# N-CW7_PWR_TWB.net
KiCad netlist of a schematic drawn in Altium Designer
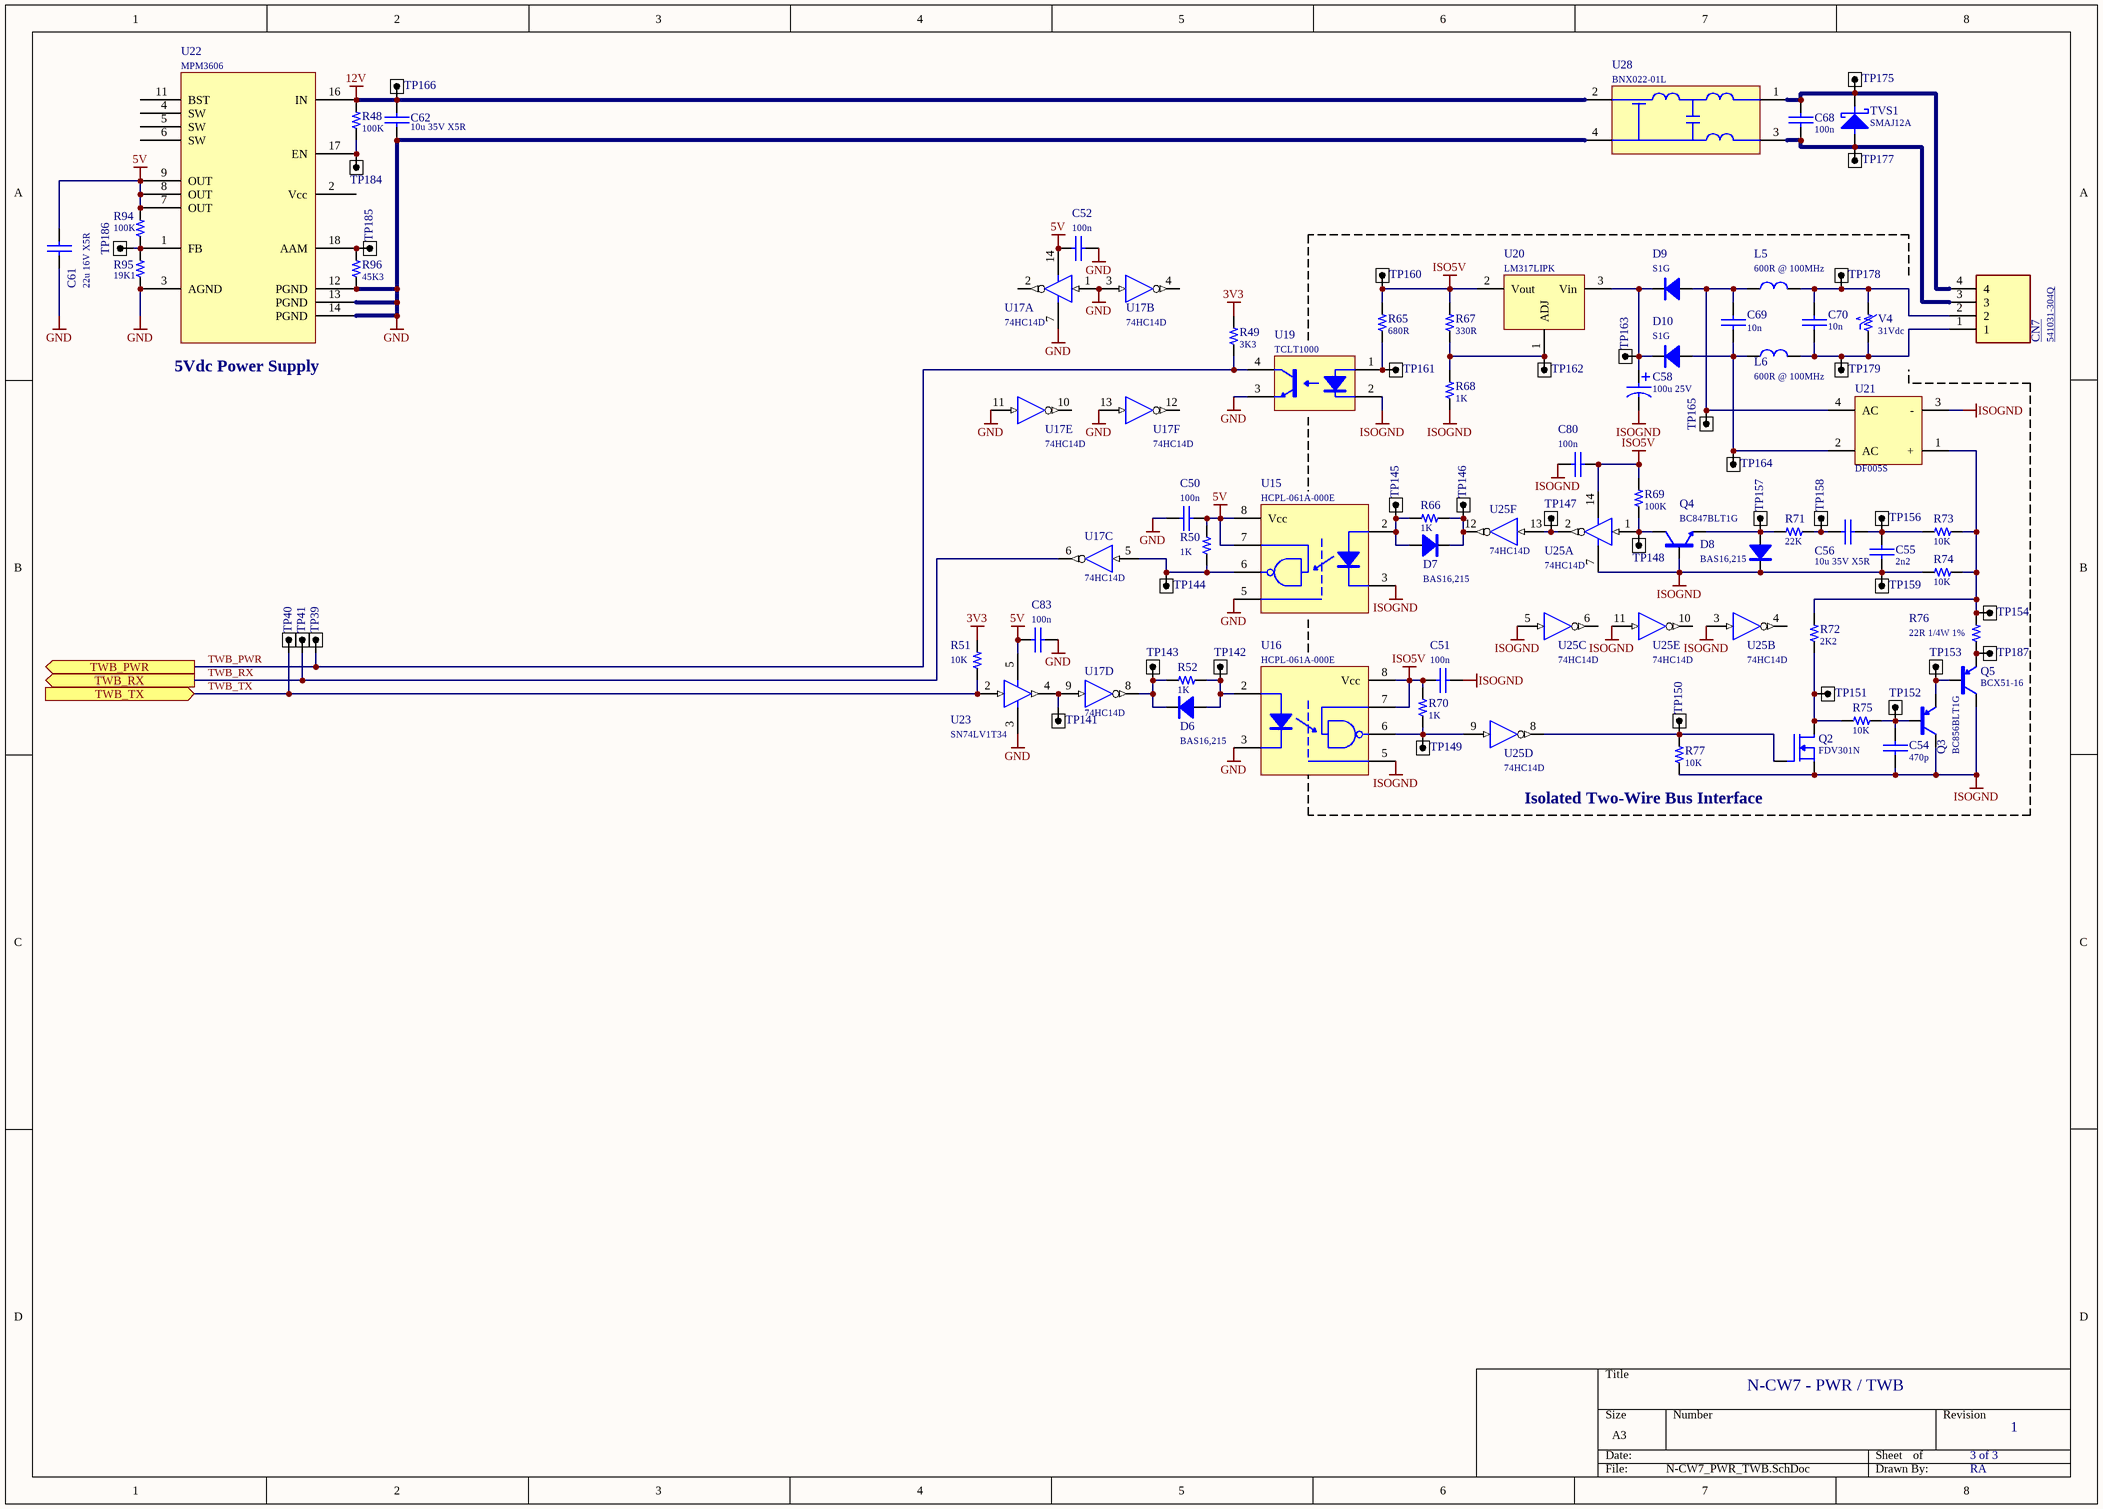
[diagram p0: N-CW7_PWR_TWB.SchDoc]

(export (version "E")
  (design (tool "Eeschema 10.0.6"))
  (components
    (comp (ref "C50")
      (value "100n")
      (footprint "TDK_0603_T0.80:CAPC1608X08N")
      (description "CAP CER 0.1UF 50V X7R 0603")
      (fields
        (field (name "MANUFACTURER") "TDK")
        (field (name "MANUFACTURER PART NUMBER") "C1608X7R1H104K080AA")
      )
      (libsource (lib "PassiveComponents_Capacitors_Ceramic") (part "TDK_0603_T0.80"))
    )
    (comp (ref "C51")
      (value "100n")
      (footprint "TDK_0603_T0.80:CAPC1608X08N")
      (description "CAP CER 0.1UF 50V X7R 0603")
      (fields
        (field (name "MANUFACTURER") "TDK")
        (field (name "MANUFACTURER PART NUMBER") "C1608X7R1H104K080AA")
      )
      (libsource (lib "PassiveComponents_Capacitors_Ceramic") (part "TDK_0603_T0.80"))
    )
    (comp (ref "C52")
      (value "100n")
      (footprint "TDK_0603_T0.80:CAPC1608X08N")
      (description "CAP CER 0.1UF 50V X7R 0603")
      (fields
        (field (name "MANUFACTURER") "TDK")
        (field (name "MANUFACTURER PART NUMBER") "C1608X7R1H104K080AA")
      )
      (libsource (lib "PassiveComponents_Capacitors_Ceramic") (part "TDK_0603_T0.80"))
    )
    (comp (ref "C54")
      (value "470p")
      (footprint "TDK_0603_T0.80:CAPC1608X08N")
      (description "CAP CER 470PF 50V C0G 0603")
      (fields
        (field (name "MANUFACTURER") "TDK")
        (field (name "MANUFACTURER PART NUMBER") "C1608C0G1H471J080AA")
      )
      (libsource (lib "PassiveComponents_Capacitors_Ceramic") (part "TDK_0603_T0.80"))
    )
    (comp (ref "C55")
      (value "2n2")
      (footprint "TDK_0603_T0.80:CAPC1608X08N")
      (description "CAP CER 2200PF 50V X7R 0603")
      (fields
        (field (name "MANUFACTURER") "TDK")
        (field (name "MANUFACTURER PART NUMBER") "C1608X7R1H222K080AE")
      )
      (libsource (lib "PassiveComponents_Capacitors_Ceramic") (part "TDK_0603_T0.80"))
    )
    (comp (ref "C56")
      (value "10u 35V X5R")
      (footprint "KEMET_1210_T1.90:CAPC3225X19N")
      (description "CAP CER 10UF 35V X5R 1210")
      (fields
        (field (name "MANUFACTURER") "KEMET")
        (field (name "MANUFACTURER PART NUMBER") "C1210C106K6PACTU")
      )
      (libsource (lib "PassiveComponents_Capacitors_Ceramic") (part "KEMET_1210_T1.90"))
    )
    (comp (ref "C58")
      (value "100u 25V")
      (footprint "KEMET_T494X/7343-43:CAPMP7343X43N")
      (description "CAP TANT 100UF 20% 25V 2917")
      (fields
        (field (name "MANUFACTURER") "KEMET")
        (field (name "MANUFACTURER PART NUMBER") "T494X107M025AT")
      )
      (libsource (lib "PassiveComponents_Capacitors_Tantalum") (part "KEMET_T494X/EIA7343-43"))
    )
    (comp (ref "C61")
      (value "22u 16V X5R")
      (footprint "TDK_0805_T1.25:CAPC2013X12N")
      (description "CAP CER 22UF 16V X5R 0805")
      (fields
        (field (name "MANUFACTURER") "TDK")
        (field (name "MANUFACTURER PART NUMBER") "C2012X5R1C226M085AC")
      )
      (libsource (lib "PassiveComponents_Capacitors_Ceramic") (part "TDK_0805_T1.25"))
    )
    (comp (ref "C62")
      (value "10u 35V X5R")
      (footprint "KEMET_1210_T1.90:CAPC3225X19N")
      (description "CAP CER 10UF 35V X5R 1210")
      (fields
        (field (name "MANUFACTURER") "KEMET")
        (field (name "MANUFACTURER PART NUMBER") "C1210C106K6PACTU")
      )
      (libsource (lib "PassiveComponents_Capacitors_Ceramic") (part "KEMET_1210_T1.90"))
    )
    (comp (ref "C68")
      (value "100n")
      (footprint "TDK_0603_T0.80:CAPC1608X08N")
      (description "CAP CER 0.1UF 50V X7R 0603")
      (fields
        (field (name "MANUFACTURER") "TDK")
        (field (name "MANUFACTURER PART NUMBER") "C1608X7R1H104K080AA")
      )
      (libsource (lib "PassiveComponents_Capacitors_Ceramic") (part "TDK_0603_T0.80"))
    )
    (comp (ref "C69")
      (value "10n")
      (footprint "TDK_0603_T0.80:CAPC1608X08N")
      (description "CAP CER 10000PF 50V X7R 0603")
      (fields
        (field (name "MANUFACTURER") "TDK")
        (field (name "MANUFACTURER PART NUMBER") "C1608X7R1H103K080AA")
      )
      (libsource (lib "PassiveComponents_Capacitors_Ceramic") (part "TDK_0603_T0.80"))
    )
    (comp (ref "C70")
      (value "10n")
      (footprint "TDK_0603_T0.80:CAPC1608X08N")
      (description "CAP CER 10000PF 50V X7R 0603")
      (fields
        (field (name "MANUFACTURER") "TDK")
        (field (name "MANUFACTURER PART NUMBER") "C1608X7R1H103K080AA")
      )
      (libsource (lib "PassiveComponents_Capacitors_Ceramic") (part "TDK_0603_T0.80"))
    )
    (comp (ref "C80")
      (value "100n")
      (footprint "TDK_0603_T0.80:CAPC1608X08N")
      (description "CAP CER 0.1UF 50V X7R 0603")
      (fields
        (field (name "MANUFACTURER") "TDK")
        (field (name "MANUFACTURER PART NUMBER") "C1608X7R1H104K080AA")
      )
      (libsource (lib "PassiveComponents_Capacitors_Ceramic") (part "TDK_0603_T0.80"))
    )
    (comp (ref "C83")
      (value "100n")
      (footprint "TDK_0603_T0.80:CAPC1608X08N")
      (description "CAP CER 0.1UF 50V X7R 0603")
      (fields
        (field (name "MANUFACTURER") "TDK")
        (field (name "MANUFACTURER PART NUMBER") "C1608X7R1H104K080AA")
      )
      (libsource (lib "PassiveComponents_Capacitors_Ceramic") (part "TDK_0603_T0.80"))
    )
    (comp (ref "CN7")
      (value "541031-304Q")
      (footprint "JWT_A2501WR2-4P:PS2.50MM")
      (description "A2501WR2-4P (JWT) 2.50mm Pitch (R-DIP)")
      (libsource (lib "Connectors") (part "JWT_A2501WR2-4P"))
    )
    (comp (ref "D6")
      (value "BAS16,215")
      (footprint "NEXPERIA_BAS16,215_SOT_23:SOT95P230X110-3N")
      (description "DIODE GP 100V 215MA SOT23")
      (fields (field (name "MANUFACTURER") "Nexperia"))
      (libsource (lib "DiscreteSemiconductors_Diodes_Rectifier") (part "NEXPERIA_BAS16,215_SOT23"))
    )
    (comp (ref "D7")
      (value "BAS16,215")
      (footprint "NEXPERIA_BAS16,215_SOT_23:SOT95P230X110-3N")
      (description "DIODE GP 100V 215MA SOT23")
      (fields (field (name "MANUFACTURER") "Nexperia"))
      (libsource (lib "DiscreteSemiconductors_Diodes_Rectifier") (part "NEXPERIA_BAS16,215_SOT23"))
    )
    (comp (ref "D8")
      (value "BAS16,215")
      (footprint "NEXPERIA_BAS16,215_SOT_23:SOT95P230X110-3N")
      (description "DIODE GP 100V 215MA SOT23")
      (fields (field (name "MANUFACTURER") "Nexperia"))
      (libsource (lib "DiscreteSemiconductors_Diodes_Rectifier") (part "NEXPERIA_BAS16,215_SOT23"))
    )
    (comp (ref "D9")
      (value "S1G")
      (footprint "DIODESINC_S1G_SMA_D0214AC:DIOM4326X24N")
      (description "DIODE GEN PURP 400V 1A SMA")
      (fields (field (name "MANUFACTURER") "Diodes") (field (name "MANUFACTURER PART NUMBER") "S1G-13-F"))
      (libsource (lib "DiscreteSemiconductors_Diodes_Rectifier") (part "DIODESINC_S1G_SMA_D0214AC"))
    )
    (comp (ref "D10")
      (value "S1G")
      (footprint "DIODESINC_S1G_SMA_D0214AC:DIOM4326X24N")
      (description "DIODE GEN PURP 400V 1A SMA")
      (fields (field (name "MANUFACTURER") "Diodes") (field (name "MANUFACTURER PART NUMBER") "S1G-13-F"))
      (libsource (lib "DiscreteSemiconductors_Diodes_Rectifier") (part "DIODESINC_S1G_SMA_D0214AC"))
    )
    (comp (ref "L5")
      (value "600R @ 100MHz")
      (footprint "LAIRD_MI0805K601R-10:INDC2012X09N")
      (description "FERRITE BEAD 600 OHM 0805 1LN")
      (fields
        (field (name "MANUFACTURER") "Laird")
        (field (name "MANUFACTURER PART NUMBER") "MI0805K601R-10")
      )
      (libsource (lib "PassiveComponents_Inductors") (part "LAIRD_MI0805K601R-10"))
    )
    (comp (ref "L6")
      (value "600R @ 100MHz")
      (footprint "LAIRD_MI0805K601R-10:INDC2012X09N")
      (description "FERRITE BEAD 600 OHM 0805 1LN")
      (fields
        (field (name "MANUFACTURER") "Laird")
        (field (name "MANUFACTURER PART NUMBER") "MI0805K601R-10")
      )
      (libsource (lib "PassiveComponents_Inductors") (part "LAIRD_MI0805K601R-10"))
    )
    (comp (ref "Q2")
      (value "FDV301N")
      (footprint "ONSEMI_FDV301N_SOT23:SOT95P230X110-3N")
      (description "MOSFET N-CH 25V 220MA SOT23")
      (fields (field (name "MANUFACTURER") "ON Semiconductor / Fairchild"))
      (libsource (lib "DiscreteSemiconductors_Transistors_JFETs") (part "ONSEMI_FDV301N_SOT23"))
    )
    (comp (ref "Q3")
      (value "BC856BLT1G")
      (footprint "ONSEMI_BC856BLT1G_SOT23_SOT95P237X110-3N")
      (description "TRANS PNP 65V 100MA SOT23-3")
      (fields (field (name "MANUFACTURER") "ON Semiconductor"))
      (libsource (lib "DiscreteSemiconductors_Transistors_BJTs") (part "ONSEMI_BC856BLT1G_SOT23"))
    )
    (comp (ref "Q4")
      (value "BC847BLT1G")
      (footprint "ONSEMI_BC847BLT1G_SOT23:SOT95P230X110-3N")
      (description "TRANS NPN 45V 100MA SOT23-3")
      (fields (field (name "MANUFACTURER") "ON Semiconductor"))
      (libsource (lib "DiscreteSemiconductors_Transistors_BJTs") (part "ONSEMI_BC847BLT1G_SOT23"))
    )
    (comp (ref "Q5")
      (value "BCX51-16")
      (footprint "INFINEON_BCX51-16_SOT89:SOT89-150P400X150-3N")
      (description "Bipolar (BJT) Transistor PNP 45 V 1 A 125MHz 2 W Surface Mount PG-SOT89")
      (fields (field (name "MANUFACTURER") "Infineon"))
      (libsource (lib "DiscreteSemiconductors_Transistors_BJTs") (part "INFINEON_BCX51-16_SOT89"))
    )
    (comp (ref "R48")
      (value "100K")
      (footprint "YAGEO_0603_T0.55:RESC1608X06N")
      (description "RES 100K OHM 1% 1/10W 0603")
      (fields
        (field (name "MANUFACTURER") "Yageo")
        (field (name "MANUFACTURER PART NUMBER") "RC0603FR-07100KL")
      )
      (libsource (lib "PassiveComponents_Resistors_ChipSMD") (part "YAGEO_0603_T0.55"))
    )
    (comp (ref "R49")
      (value "3K3")
      (footprint "YAGEO_0603_T0.55:RESC1608X06N")
      (description "RC0603FR-07XXXL")
      (fields
        (field (name "MANUFACTURER") "Yageo")
        (field (name "MANUFACTURER PART NUMBER") "RC0603FR-073K3L")
      )
      (libsource (lib "PassiveComponents_Resistors_ChipSMD") (part "YAGEO_0603_T0.55"))
    )
    (comp (ref "R50")
      (value "1K")
      (footprint "YAGEO_0603_T0.55:RESC1608X06N")
      (description "RES 1K OHM 1% 1/10W 0603")
      (fields
        (field (name "MANUFACTURER") "Yageo")
        (field (name "MANUFACTURER PART NUMBER") "RC0603FR-071KL")
      )
      (libsource (lib "PassiveComponents_Resistors_ChipSMD") (part "YAGEO_0603_T0.55"))
    )
    (comp (ref "R51")
      (value "10K")
      (footprint "YAGEO_0603_T0.55:RESC1608X06N")
      (description "RES 10K OHM 1% 1/10W 0603")
      (fields
        (field (name "MANUFACTURER") "Yageo")
        (field (name "MANUFACTURER PART NUMBER") "RC0603FR-0710KL")
      )
      (libsource (lib "PassiveComponents_Resistors_ChipSMD") (part "YAGEO_0603_T0.55"))
    )
    (comp (ref "R52")
      (value "1K")
      (footprint "YAGEO_0603_T0.55:RESC1608X06N")
      (description "RES 1K OHM 1% 1/10W 0603")
      (fields
        (field (name "MANUFACTURER") "Yageo")
        (field (name "MANUFACTURER PART NUMBER") "RC0603FR-071KL")
      )
      (libsource (lib "PassiveComponents_Resistors_ChipSMD") (part "YAGEO_0603_T0.55"))
    )
    (comp (ref "R65")
      (value "680R")
      (footprint "YAGEO_0603_T0.55:RESC1608X06N")
      (description "RES 680 OHM 1% 1/10W 0603")
      (fields
        (field (name "MANUFACTURER") "Yageo")
        (field (name "MANUFACTURER PART NUMBER") "RC0603FR-07680RL")
      )
      (libsource (lib "PassiveComponents_Resistors_ChipSMD") (part "YAGEO_0603_T0.55"))
    )
    (comp (ref "R66")
      (value "1K")
      (footprint "YAGEO_0603_T0.55:RESC1608X06N")
      (description "RES 1K OHM 1% 1/10W 0603")
      (fields
        (field (name "MANUFACTURER") "Yageo")
        (field (name "MANUFACTURER PART NUMBER") "RC0603FR-071KL")
      )
      (libsource (lib "PassiveComponents_Resistors_ChipSMD") (part "YAGEO_0603_T0.55"))
    )
    (comp (ref "R67")
      (value "330R")
      (footprint "YAGEO_0603_T0.55:RESC1608X06N")
      (description "RES 330 OHM 1% 1/10W 0603")
      (fields
        (field (name "MANUFACTURER") "Yageo")
        (field (name "MANUFACTURER PART NUMBER") "RC0603FR-07330RL")
      )
      (libsource (lib "PassiveComponents_Resistors_ChipSMD") (part "YAGEO_0603_T0.55"))
    )
    (comp (ref "R68")
      (value "1K")
      (footprint "YAGEO_0603_T0.55:RESC1608X06N")
      (description "RES 1K OHM 1% 1/10W 0603")
      (fields
        (field (name "MANUFACTURER") "Yageo")
        (field (name "MANUFACTURER PART NUMBER") "RC0603FR-071KL")
      )
      (libsource (lib "PassiveComponents_Resistors_ChipSMD") (part "YAGEO_0603_T0.55"))
    )
    (comp (ref "R69")
      (value "100K")
      (footprint "YAGEO_0603_T0.55:RESC1608X06N")
      (description "RES 100K OHM 1% 1/10W 0603")
      (fields
        (field (name "MANUFACTURER") "Yageo")
        (field (name "MANUFACTURER PART NUMBER") "RC0603FR-07100KL")
      )
      (libsource (lib "PassiveComponents_Resistors_ChipSMD") (part "YAGEO_0603_T0.55"))
    )
    (comp (ref "R70")
      (value "1K")
      (footprint "YAGEO_0603_T0.55:RESC1608X06N")
      (description "RES 1K OHM 1% 1/10W 0603")
      (fields
        (field (name "MANUFACTURER") "Yageo")
        (field (name "MANUFACTURER PART NUMBER") "RC0603FR-071KL")
      )
      (libsource (lib "PassiveComponents_Resistors_ChipSMD") (part "YAGEO_0603_T0.55"))
    )
    (comp (ref "R71")
      (value "22K")
      (footprint "YAGEO_0603_T0.55:RESC1608X06N")
      (description "RES 22K OHM 1% 1/10W 0603")
      (fields
        (field (name "MANUFACTURER") "Yageo")
        (field (name "MANUFACTURER PART NUMBER") "RC0603FR-0722KL")
      )
      (libsource (lib "PassiveComponents_Resistors_ChipSMD") (part "YAGEO_0603_T0.55"))
    )
    (comp (ref "R72")
      (value "2K2")
      (footprint "YAGEO_0603_T0.55:RESC1608X06N")
      (description "RES 2.2K OHM 1% 1/10W 0603")
      (fields
        (field (name "MANUFACTURER") "Yageo")
        (field (name "MANUFACTURER PART NUMBER") "RC0603FR-072K2L")
      )
      (libsource (lib "PassiveComponents_Resistors_ChipSMD") (part "YAGEO_0603_T0.55"))
    )
    (comp (ref "R73")
      (value "10K")
      (footprint "YAGEO_0603_T0.55:RESC1608X06N")
      (description "RES 10K OHM 1% 1/10W 0603")
      (fields
        (field (name "MANUFACTURER") "Yageo")
        (field (name "MANUFACTURER PART NUMBER") "RC0603FR-0710KL")
      )
      (libsource (lib "PassiveComponents_Resistors_ChipSMD") (part "YAGEO_0603_T0.55"))
    )
    (comp (ref "R74")
      (value "10K")
      (footprint "YAGEO_0603_T0.55:RESC1608X06N")
      (description "RES 10K OHM 1% 1/10W 0603")
      (fields
        (field (name "MANUFACTURER") "Yageo")
        (field (name "MANUFACTURER PART NUMBER") "RC0603FR-0710KL")
      )
      (libsource (lib "PassiveComponents_Resistors_ChipSMD") (part "YAGEO_0603_T0.55"))
    )
    (comp (ref "R75")
      (value "10K")
      (footprint "YAGEO_0603_T0.55:RESC1608X06N")
      (description "RES 10K OHM 1% 1/10W 0603")
      (fields
        (field (name "MANUFACTURER") "Yageo")
        (field (name "MANUFACTURER PART NUMBER") "RC0603FR-0710KL")
      )
      (libsource (lib "PassiveComponents_Resistors_ChipSMD") (part "YAGEO_0603_T0.55"))
    )
    (comp (ref "R76")
      (value "22R 1/4W 1%")
      (footprint "YAGEO_1206_T0.55:RESC3116X06N")
      (description "RES 22 OHM 1% 1/4W 1206")
      (fields
        (field (name "MANUFACTURER") "Yageo")
        (field (name "MANUFACTURER PART NUMBER") "RC1206FR-0722RL")
      )
      (libsource (lib "PassiveComponents_Resistors_ChipSMD") (part "YAGEO_1206_T0.55"))
    )
    (comp (ref "R77")
      (value "10K")
      (footprint "YAGEO_0603_T0.55:RESC1608X06N")
      (description "RES 10K OHM 1% 1/10W 0603")
      (fields
        (field (name "MANUFACTURER") "Yageo")
        (field (name "MANUFACTURER PART NUMBER") "RC0603FR-0710KL")
      )
      (libsource (lib "PassiveComponents_Resistors_ChipSMD") (part "YAGEO_0603_T0.55"))
    )
    (comp (ref "R94")
      (value "100K")
      (footprint "YAGEO_0603_T0.55:RESC1608X06N")
      (description "RES 100K OHM 1% 1/10W 0603")
      (fields
        (field (name "MANUFACTURER") "Yageo")
        (field (name "MANUFACTURER PART NUMBER") "RC0603FR-07100KL")
      )
      (libsource (lib "PassiveComponents_Resistors_ChipSMD") (part "YAGEO_0603_T0.55"))
    )
    (comp (ref "R95")
      (value "19K1")
      (footprint "YAGEO_0603_T0.55:RESC1608X06N")
      (description "RES 19.1K OHM 1% 1/10W 0603")
      (fields
        (field (name "MANUFACTURER") "Yageo")
        (field (name "MANUFACTURER PART NUMBER") "RC0603FR-0719K1L")
      )
      (libsource (lib "PassiveComponents_Resistors_ChipSMD") (part "YAGEO_0603_T0.55"))
    )
    (comp (ref "R96")
      (value "45K3")
      (footprint "YAGEO_0603_T0.55:RESC1608X06N")
      (description "RES 45.3K OHM 1% 1/10W 0603")
      (fields
        (field (name "MANUFACTURER") "Yageo")
        (field (name "MANUFACTURER PART NUMBER") "RC0603FR-0745K3L")
      )
      (libsource (lib "PassiveComponents_Resistors_ChipSMD") (part "YAGEO_0603_T0.55"))
    )
    (comp (ref "TP39")
      (value "TESTPOINT_OCTAGONAL")
      (footprint "TESTPOINT_OCTAGONAL")
      (libsource (lib "Miscellaneous") (part "TESTPOINT_OCTAGONAL"))
    )
    (comp (ref "TP40")
      (value "TESTPOINT_OCTAGONAL")
      (footprint "TESTPOINT_OCTAGONAL")
      (libsource (lib "Miscellaneous") (part "TESTPOINT_OCTAGONAL"))
    )
    (comp (ref "TP41")
      (value "TESTPOINT_OCTAGONAL")
      (footprint "TESTPOINT_OCTAGONAL")
      (libsource (lib "Miscellaneous") (part "TESTPOINT_OCTAGONAL"))
    )
    (comp (ref "TP141")
      (value "TESTPOINT_OCTAGONAL")
      (footprint "TESTPOINT_OCTAGONAL")
      (libsource (lib "") (part "TESTPOINT_OCTAGONAL_2"))
    )
    (comp (ref "TP142")
      (value "TESTPOINT_OCTAGONAL")
      (footprint "TESTPOINT_OCTAGONAL")
      (libsource (lib "Miscellaneous") (part "TESTPOINT_OCTAGONAL"))
    )
    (comp (ref "TP143")
      (value "TESTPOINT_OCTAGONAL")
      (footprint "TESTPOINT_OCTAGONAL")
      (libsource (lib "Miscellaneous") (part "TESTPOINT_OCTAGONAL"))
    )
    (comp (ref "TP144")
      (value "TESTPOINT_OCTAGONAL")
      (footprint "TESTPOINT_OCTAGONAL")
      (libsource (lib "") (part "TESTPOINT_OCTAGONAL_2"))
    )
    (comp (ref "TP145")
      (value "TESTPOINT_OCTAGONAL")
      (footprint "TESTPOINT_OCTAGONAL")
      (libsource (lib "Miscellaneous") (part "TESTPOINT_OCTAGONAL"))
    )
    (comp (ref "TP146")
      (value "TESTPOINT_OCTAGONAL")
      (footprint "TESTPOINT_OCTAGONAL")
      (libsource (lib "Miscellaneous") (part "TESTPOINT_OCTAGONAL"))
    )
    (comp (ref "TP147")
      (value "TESTPOINT_OCTAGONAL")
      (footprint "TESTPOINT_OCTAGONAL")
      (libsource (lib "Miscellaneous") (part "TESTPOINT_OCTAGONAL"))
    )
    (comp (ref "TP148")
      (value "TESTPOINT_OCTAGONAL")
      (footprint "TESTPOINT_OCTAGONAL")
      (libsource (lib "") (part "TESTPOINT_OCTAGONAL_2"))
    )
    (comp (ref "TP149")
      (value "TESTPOINT_OCTAGONAL")
      (footprint "TESTPOINT_OCTAGONAL")
      (libsource (lib "") (part "TESTPOINT_OCTAGONAL_2"))
    )
    (comp (ref "TP150")
      (value "TESTPOINT_OCTAGONAL")
      (footprint "TESTPOINT_OCTAGONAL")
      (libsource (lib "Miscellaneous") (part "TESTPOINT_OCTAGONAL"))
    )
    (comp (ref "TP151")
      (value "TESTPOINT_OCTAGONAL")
      (footprint "TESTPOINT_OCTAGONAL")
      (libsource (lib "") (part "TESTPOINT_OCTAGONAL_3"))
    )
    (comp (ref "TP152")
      (value "TESTPOINT_OCTAGONAL")
      (footprint "TESTPOINT_OCTAGONAL")
      (libsource (lib "Miscellaneous") (part "TESTPOINT_OCTAGONAL"))
    )
    (comp (ref "TP153")
      (value "TESTPOINT_OCTAGONAL")
      (footprint "TESTPOINT_OCTAGONAL")
      (libsource (lib "Miscellaneous") (part "TESTPOINT_OCTAGONAL"))
    )
    (comp (ref "TP154")
      (value "TESTPOINT_OCTAGONAL")
      (footprint "TESTPOINT_OCTAGONAL")
      (libsource (lib "") (part "TESTPOINT_OCTAGONAL_3"))
    )
    (comp (ref "TP156")
      (value "TESTPOINT_OCTAGONAL")
      (footprint "TESTPOINT_OCTAGONAL")
      (libsource (lib "Miscellaneous") (part "TESTPOINT_OCTAGONAL"))
    )
    (comp (ref "TP157")
      (value "TESTPOINT_OCTAGONAL")
      (footprint "TESTPOINT_OCTAGONAL")
      (libsource (lib "Miscellaneous") (part "TESTPOINT_OCTAGONAL"))
    )
    (comp (ref "TP158")
      (value "TESTPOINT_OCTAGONAL")
      (footprint "TESTPOINT_OCTAGONAL")
      (libsource (lib "Miscellaneous") (part "TESTPOINT_OCTAGONAL"))
    )
    (comp (ref "TP159")
      (value "TESTPOINT_OCTAGONAL")
      (footprint "TESTPOINT_OCTAGONAL")
      (libsource (lib "") (part "TESTPOINT_OCTAGONAL_2"))
    )
    (comp (ref "TP160")
      (value "TESTPOINT_OCTAGONAL")
      (footprint "TESTPOINT_OCTAGONAL")
      (libsource (lib "Miscellaneous") (part "TESTPOINT_OCTAGONAL"))
    )
    (comp (ref "TP161")
      (value "TESTPOINT_OCTAGONAL")
      (footprint "TESTPOINT_OCTAGONAL")
      (libsource (lib "") (part "TESTPOINT_OCTAGONAL_3"))
    )
    (comp (ref "TP162")
      (value "TESTPOINT_OCTAGONAL")
      (footprint "TESTPOINT_OCTAGONAL")
      (libsource (lib "") (part "TESTPOINT_OCTAGONAL_2"))
    )
    (comp (ref "TP163")
      (value "TESTPOINT_OCTAGONAL")
      (footprint "TESTPOINT_OCTAGONAL")
      (libsource (lib "") (part "TESTPOINT_OCTAGONAL_1"))
    )
    (comp (ref "TP164")
      (value "TESTPOINT_OCTAGONAL")
      (footprint "TESTPOINT_OCTAGONAL")
      (libsource (lib "") (part "TESTPOINT_OCTAGONAL_2"))
    )
    (comp (ref "TP165")
      (value "TESTPOINT_OCTAGONAL")
      (footprint "TESTPOINT_OCTAGONAL")
      (libsource (lib "") (part "TESTPOINT_OCTAGONAL_2"))
    )
    (comp (ref "TP166")
      (value "TESTPOINT_OCTAGONAL")
      (footprint "TESTPOINT_OCTAGONAL")
      (libsource (lib "Miscellaneous") (part "TESTPOINT_OCTAGONAL"))
    )
    (comp (ref "TP175")
      (value "TESTPOINT_OCTAGONAL")
      (footprint "TESTPOINT_OCTAGONAL")
      (libsource (lib "Miscellaneous") (part "TESTPOINT_OCTAGONAL"))
    )
    (comp (ref "TP177")
      (value "TESTPOINT_OCTAGONAL")
      (footprint "TESTPOINT_OCTAGONAL")
      (libsource (lib "") (part "TESTPOINT_OCTAGONAL_2"))
    )
    (comp (ref "TP178")
      (value "TESTPOINT_OCTAGONAL")
      (footprint "TESTPOINT_OCTAGONAL")
      (libsource (lib "Miscellaneous") (part "TESTPOINT_OCTAGONAL"))
    )
    (comp (ref "TP179")
      (value "TESTPOINT_OCTAGONAL")
      (footprint "TESTPOINT_OCTAGONAL")
      (libsource (lib "") (part "TESTPOINT_OCTAGONAL_2"))
    )
    (comp (ref "TP184")
      (value "TESTPOINT_OCTAGONAL")
      (footprint "TESTPOINT_OCTAGONAL")
      (libsource (lib "") (part "TESTPOINT_OCTAGONAL_2"))
    )
    (comp (ref "TP185")
      (value "TESTPOINT_OCTAGONAL")
      (footprint "TESTPOINT_OCTAGONAL")
      (libsource (lib "") (part "TESTPOINT_OCTAGONAL_3"))
    )
    (comp (ref "TP186")
      (value "TESTPOINT_OCTAGONAL")
      (footprint "TESTPOINT_OCTAGONAL")
      (libsource (lib "") (part "TESTPOINT_OCTAGONAL_1"))
    )
    (comp (ref "TP187")
      (value "TESTPOINT_OCTAGONAL")
      (footprint "TESTPOINT_OCTAGONAL")
      (libsource (lib "") (part "TESTPOINT_OCTAGONAL_3"))
    )
    (comp (ref "TVS1")
      (value "SMAJ12A")
      (footprint "LITTELFUSE_SMAJ12A_D0214AC:DIOM4326X23N")
      (description "TVS DIODE 12VWM 19.9VC DO214AC")
      (fields (field (name "MANUFACTURER") "Littelfuse"))
      (libsource (lib "CircuitProtection_TVSDiodes") (part "LITTELFUSE_SMAJ12A_D0214AC"))
    )
    (comp (ref "U15")
      (value "HCPL-061A-000E")
      (footprint "BROADCOM_HCPL-061A-000E:SOIC127P600X338-8N")
      (description "OPTOISO 3.75KV OPN COLL 8SO TALL")
      (fields (field (name "MANUFACTURER") "Broadcom Avago"))
      (libsource (lib "OptoElectronics_OptoCouplers") (part "BROADCOM_HCPL-061A-000E"))
    )
    (comp (ref "U16")
      (value "HCPL-061A-000E")
      (footprint "BROADCOM_HCPL-061A-000E:SOIC127P600X338-8N")
      (description "OPTOISO 3.75KV OPN COLL 8SO TALL")
      (fields (field (name "MANUFACTURER") "Broadcom Avago"))
      (libsource (lib "") (part "BROADCOM_HCPL-061A-000E_1"))
    )
    (comp (ref "U17")
      (value "74HC14D")
      (footprint "NEXPERIA_74HC14D_SO14:SOIC127P600X175-14N")
      (description "IC HEX INVERTER SCHM TRIG 14SOIC")
      (fields
        (field (name "MANUFACTURER") "Nexperia")
        (field (name "MANUFACTURER PART NUMBER") "74HC14D,653")
      )
      (libsource (lib "IntegratedCircuits_Logic_Gates") (part "NEXPERIA_74HC14D_SO14"))
    )
    (comp (ref "U19")
      (value "TCLT1000")
      (footprint "VISHAY_TCLT1000_SOP4L:SOP254P1020X230-4N")
      (description "OPTOISOLATOR 5KV 1CH TRANS 4-SOP")
      (fields (field (name "MANUFACTURER") "Vishay"))
      (libsource (lib "OptoElectronics_OptoCouplers") (part "VISHAY_TCLT1000_SOP4L"))
    )
    (comp (ref "U20")
      (value "LM317LIPK")
      (footprint "TI_LM317LIPK_SOT89:SOT89-150P350X160-3N")
      (description "IC REG LIN POS ADJ 100MA SOT89-3")
      (fields (field (name "MANUFACTURER") "Texas Instruments"))
      (libsource (lib "IntegratedCircuits_Power_VoltageRegsLinear") (part "TI_LM317LIPK_SOT89"))
    )
    (comp (ref "U21")
      (value "DF005S")
      (footprint "DIODESINC_DF005S:SOP520P1040X265-4N")
      (description "BRIDGE RECT 1PHASE 50V 1A DFS")
      (fields (field (name "MANUFACTURER") "Diodes"))
      (libsource (lib "DiscreteSemiconductors_Diodes_Rectifier") (part "DIODESINC_DF005S"))
    )
    (comp (ref "U22")
      (value "MPM3606")
      (footprint "MPS_MPM3606GQV-P")
      (description "DC DC CONVERTER 0.8-5.5V")
      (fields
        (field (name "MANUFACTURER") "Monolithic Power Systems")
        (field (name "MANUFACTURER PART NUMBER") "MPM3606GQV-P")
      )
      (libsource (lib "IntegratedCircuits_Power_VoltageRegsSwitchMode") (part "MPS_MPM3606GQV-P"))
    )
    (comp (ref "U23")
      (value "SN74LV1T34")
      (footprint "TI_SN74LV1T34_SOT23_5:SOT95P280X145-5N")
      (description "IC BUF NON-INVERT 5.5V SOT23-5")
      (fields
        (field (name "MANUFACTURER") "Texas Instruments")
        (field (name "MANUFACTURER PART NUMBER") "SN74LV1T34DBVR")
      )
      (libsource (lib "IntegratedCircuits_Logic_Gates") (part "TI_SN74LV1T34_SOT23_5"))
    )
    (comp (ref "U25")
      (value "74HC14D")
      (footprint "NEXPERIA_74HC14D_SO14:SOIC127P600X175-14N")
      (description "IC HEX INVERTER SCHM TRIG 14SOIC")
      (fields
        (field (name "MANUFACTURER") "Nexperia")
        (field (name "MANUFACTURER PART NUMBER") "74HC14D,653")
      )
      (libsource (lib "IntegratedCircuits_Logic_Gates") (part "NEXPERIA_74HC14D_SO14"))
    )
    (comp (ref "U28")
      (value "BNX022-01L")
      (footprint "MURATA_BNX022-01L")
      (description "FILTER LC 1UF SMD")
      (fields (field (name "MANUFACTURER") "Murata"))
      (libsource (lib "PassiveComponents_LCFilters") (part "MURATA_BNX022-01L"))
    )
    (comp (ref "V4")
      (value "31Vdc")
      (footprint "TDK_B72520_1206:INDC3216X17N")
      (description "VARISTOR 39V 200A 1206")
      (fields
        (field (name "MANUFACTURER") "TDK EPCOS")
        (field (name "MANUFACTURER PART NUMBER") "B72520T0250K062")
      )
      (libsource (lib "CircuitProtection_Varistors") (part "TDK_B72520_1206"))
    )
  )
  (nets
    (net (code "1") (name "/TWB_PWR") (class "Default")
      (node (ref "R49") (pin "1") (pinfunction "1_1") (pintype "passive"))
      (node (ref "TP39") (pin "1") (pinfunction "1_1") (pintype "passive"))
      (node (ref "U19") (pin "4") (pinfunction "4_4") (pintype "passive"))
    )
    (net (code "2") (name "/TWB_RX") (class "Default")
      (node (ref "TP41") (pin "1") (pinfunction "1_1") (pintype "passive"))
      (node (ref "U17") (pin "6") (pinfunction "Y3_6") (pintype "output"))
    )
    (net (code "3") (name "/TWB_TX") (class "Default")
      (node (ref "R51") (pin "2") (pinfunction "2_2") (pintype "passive"))
      (node (ref "TP40") (pin "1") (pinfunction "1_1") (pintype "passive"))
      (node (ref "U23") (pin "2") (pinfunction "A_2") (pintype "input"))
    )
    (net (code "4") (name "3V3") (class "Default")
      (node (ref "R49") (pin "2") (pinfunction "2_2") (pintype "passive"))
      (node (ref "R51") (pin "1") (pinfunction "1_1") (pintype "passive"))
    )
    (net (code "5") (name "5V") (class "Default")
      (node (ref "C50") (pin "2") (pinfunction "2_2") (pintype "passive"))
      (node (ref "C52") (pin "1") (pinfunction "1_1") (pintype "passive"))
      (node (ref "C61") (pin "2") (pinfunction "2_2") (pintype "passive"))
      (node (ref "C83") (pin "1") (pinfunction "1_1") (pintype "passive"))
      (node (ref "R50") (pin "1") (pinfunction "1_1") (pintype "passive"))
      (node (ref "R94") (pin "1") (pinfunction "1_1") (pintype "passive"))
      (node (ref "U15") (pin "7") (pintype "passive"))
      (node (ref "U15") (pin "8") (pinfunction "Vcc_8") (pintype "power_in"))
      (node (ref "U17") (pin "14") (pinfunction "Vcc_14") (pintype "power_in"))
      (node (ref "U22") (pin "7") (pinfunction "OUT_7") (pintype "passive"))
      (node (ref "U22") (pin "8") (pinfunction "OUT_8") (pintype "passive"))
      (node (ref "U22") (pin "9") (pinfunction "OUT_9") (pintype "passive"))
      (node (ref "U23") (pin "5") (pinfunction "Vcc_5") (pintype "power_in"))
    )
    (net (code "6") (name "12V") (class "Default")
      (node (ref "C62") (pin "2") (pinfunction "2_2") (pintype "passive"))
      (node (ref "R48") (pin "1") (pinfunction "1_1") (pintype "passive"))
      (node (ref "TP166") (pin "1") (pinfunction "1_1") (pintype "passive"))
      (node (ref "U22") (pin "16") (pinfunction "IN_16") (pintype "passive"))
      (node (ref "U28") (pin "2") (pinfunction "CB_2") (pintype "passive"))
    )
    (net (code "7") (name "GND") (class "Default")
      (node (ref "C50") (pin "1") (pinfunction "1_1") (pintype "passive"))
      (node (ref "C52") (pin "2") (pinfunction "2_2") (pintype "passive"))
      (node (ref "C61") (pin "1") (pinfunction "1_1") (pintype "passive"))
      (node (ref "C62") (pin "1") (pinfunction "1_1") (pintype "passive"))
      (node (ref "C83") (pin "2") (pinfunction "2_2") (pintype "passive"))
      (node (ref "R95") (pin "2") (pinfunction "2_2") (pintype "passive"))
      (node (ref "R96") (pin "1") (pinfunction "1_1") (pintype "passive"))
      (node (ref "U15") (pin "5") (pintype "power_in"))
      (node (ref "U16") (pin "3") (pintype "passive"))
      (node (ref "U17") (pin "1") (pinfunction "A1_1") (pintype "input"))
      (node (ref "U17") (pin "11") (pinfunction "A5_11") (pintype "input"))
      (node (ref "U17") (pin "13") (pinfunction "A6_13") (pintype "input"))
      (node (ref "U17") (pin "3") (pinfunction "A2_3") (pintype "input"))
      (node (ref "U17") (pin "7") (pinfunction "GND_7") (pintype "power_in"))
      (node (ref "U19") (pin "3") (pinfunction "3_3") (pintype "passive"))
      (node (ref "U22") (pin "12") (pinfunction "PGND_12") (pintype "passive"))
      (node (ref "U22") (pin "13") (pinfunction "PGND_13") (pintype "passive"))
      (node (ref "U22") (pin "14") (pinfunction "PGND_14") (pintype "passive"))
      (node (ref "U22") (pin "3") (pinfunction "AGND_3") (pintype "passive"))
      (node (ref "U23") (pin "3") (pinfunction "GND_3") (pintype "power_in"))
      (node (ref "U28") (pin "4") (pinfunction "CG_4") (pintype "passive"))
    )
    (net (code "8") (name "ISO5V") (class "Default")
      (node (ref "C51") (pin "1") (pinfunction "1_1") (pintype "passive"))
      (node (ref "C80") (pin "2") (pinfunction "2_2") (pintype "passive"))
      (node (ref "R65") (pin "2") (pinfunction "2_2") (pintype "passive"))
      (node (ref "R67") (pin "1") (pinfunction "1_1") (pintype "passive"))
      (node (ref "R69") (pin "1") (pinfunction "1_1") (pintype "passive"))
      (node (ref "R70") (pin "1") (pinfunction "1_1") (pintype "passive"))
      (node (ref "TP160") (pin "1") (pinfunction "1_1") (pintype "passive"))
      (node (ref "U16") (pin "7") (pintype "passive"))
      (node (ref "U16") (pin "8") (pinfunction "Vcc_8") (pintype "power_in"))
      (node (ref "U20") (pin "2") (pinfunction "Vout_2") (pintype "passive"))
      (node (ref "U25") (pin "14") (pinfunction "Vcc_14") (pintype "power_in"))
    )
    (net (code "9") (name "ISOGND") (class "Default")
      (node (ref "C51") (pin "2") (pinfunction "2_2") (pintype "passive"))
      (node (ref "C54") (pin "1") (pinfunction "1_1") (pintype "passive"))
      (node (ref "C55") (pin "1") (pinfunction "1_1") (pintype "passive"))
      (node (ref "C58") (pin "2") (pinfunction "2_2") (pintype "passive"))
      (node (ref "C80") (pin "1") (pinfunction "1_1") (pintype "passive"))
      (node (ref "D8") (pin "3") (pinfunction "K_3") (pintype "passive"))
      (node (ref "Q2") (pin "2") (pinfunction "S_2") (pintype "passive"))
      (node (ref "Q3") (pin "3") (pinfunction "C_3") (pintype "passive"))
      (node (ref "Q4") (pin "1") (pinfunction "B_1") (pintype "passive"))
      (node (ref "Q5") (pin "2") (pinfunction "C_2") (pintype "passive"))
      (node (ref "R68") (pin "2") (pinfunction "2_2") (pintype "passive"))
      (node (ref "R74") (pin "1") (pinfunction "1_1") (pintype "passive"))
      (node (ref "R77") (pin "1") (pinfunction "1_1") (pintype "passive"))
      (node (ref "TP159") (pin "1") (pinfunction "1_1") (pintype "passive"))
      (node (ref "U15") (pin "3") (pintype "passive"))
      (node (ref "U16") (pin "5") (pintype "power_in"))
      (node (ref "U19") (pin "2") (pinfunction "2_2") (pintype "passive"))
      (node (ref "U21") (pin "3") (pinfunction "-_3") (pintype "passive"))
      (node (ref "U25") (pin "11") (pinfunction "A5_11") (pintype "input"))
      (node (ref "U25") (pin "3") (pinfunction "A2_3") (pintype "input"))
      (node (ref "U25") (pin "5") (pinfunction "A3_5") (pintype "input"))
      (node (ref "U25") (pin "7") (pinfunction "GND_7") (pintype "power_in"))
    )
    (net (code "10") (name "Net-(C55-Pad2)") (class "Default")
      (node (ref "C55") (pin "2") (pinfunction "2_2") (pintype "passive"))
      (node (ref "C56") (pin "1") (pinfunction "1_1") (pintype "passive"))
      (node (ref "R73") (pin "1") (pinfunction "1_1") (pintype "passive"))
      (node (ref "TP156") (pin "1") (pinfunction "1_1") (pintype "passive"))
    )
    (net (code "11") (name "Net-(C56-Pad2)") (class "Default")
      (node (ref "C56") (pin "2") (pinfunction "2_2") (pintype "passive"))
      (node (ref "R71") (pin "2") (pinfunction "2_2") (pintype "passive"))
      (node (ref "TP158") (pin "1") (pinfunction "1_1") (pintype "passive"))
    )
    (net (code "12") (name "Net-(C70-Pad1)") (class "Default")
      (node (ref "C70") (pin "1") (pinfunction "1_1") (pintype "passive"))
      (node (ref "CN7") (pin "1") (pinfunction "1_1") (pintype "passive"))
      (node (ref "L6") (pin "2") (pinfunction "2_2") (pintype "passive"))
      (node (ref "TP179") (pin "1") (pinfunction "1_1") (pintype "passive"))
      (node (ref "V4") (pin "2") (pinfunction "2_2") (pintype "passive"))
    )
    (net (code "13") (name "Net-(C70-Pad2)") (class "Default")
      (node (ref "C70") (pin "2") (pinfunction "2_2") (pintype "passive"))
      (node (ref "CN7") (pin "2") (pinfunction "2_2") (pintype "passive"))
      (node (ref "L5") (pin "2") (pinfunction "2_2") (pintype "passive"))
      (node (ref "TP178") (pin "1") (pinfunction "1_1") (pintype "passive"))
      (node (ref "V4") (pin "1") (pinfunction "1_1") (pintype "passive"))
    )
    (net (code "14") (name "Net-(D6-A)") (class "Default")
      (node (ref "D6") (pin "1") (pinfunction "A_1") (pintype "passive"))
      (node (ref "R52") (pin "2") (pinfunction "2_2") (pintype "passive"))
      (node (ref "TP142") (pin "1") (pinfunction "1_1") (pintype "passive"))
      (node (ref "U16") (pin "2") (pintype "passive"))
    )
    (net (code "15") (name "Net-(D6-K)") (class "Default")
      (node (ref "D6") (pin "3") (pinfunction "K_3") (pintype "passive"))
      (node (ref "R52") (pin "1") (pinfunction "1_1") (pintype "passive"))
      (node (ref "TP143") (pin "1") (pinfunction "1_1") (pintype "passive"))
      (node (ref "U17") (pin "8") (pinfunction "Y4_8") (pintype "output"))
    )
    (net (code "16") (name "Net-(D7-A)") (class "Default")
      (node (ref "D7") (pin "1") (pinfunction "A_1") (pintype "passive"))
      (node (ref "R66") (pin "2") (pinfunction "2_2") (pintype "passive"))
      (node (ref "TP145") (pin "1") (pinfunction "1_1") (pintype "passive"))
      (node (ref "U15") (pin "2") (pintype "passive"))
    )
    (net (code "17") (name "Net-(D7-K)") (class "Default")
      (node (ref "D7") (pin "3") (pinfunction "K_3") (pintype "passive"))
      (node (ref "R66") (pin "1") (pinfunction "1_1") (pintype "passive"))
      (node (ref "TP146") (pin "1") (pinfunction "1_1") (pintype "passive"))
      (node (ref "U25") (pin "12") (pinfunction "Y6_12") (pintype "output"))
    )
    (net (code "18") (name "Net-(D8-A)") (class "Default")
      (node (ref "D8") (pin "1") (pinfunction "A_1") (pintype "passive"))
      (node (ref "Q4") (pin "2") (pinfunction "E_2") (pintype "passive"))
      (node (ref "R71") (pin "1") (pinfunction "1_1") (pintype "passive"))
      (node (ref "TP157") (pin "1") (pinfunction "1_1") (pintype "passive"))
    )
    (net (code "19") (name "Net-(D9-A)") (class "Default")
      (node (ref "C69") (pin "2") (pinfunction "2_2") (pintype "passive"))
      (node (ref "D9") (pin "2") (pinfunction "A_2") (pintype "passive"))
      (node (ref "L5") (pin "1") (pinfunction "1_1") (pintype "passive"))
      (node (ref "TP165") (pin "1") (pinfunction "1_1") (pintype "passive"))
      (node (ref "U21") (pin "4") (pinfunction "AC_4") (pintype "passive"))
    )
    (net (code "20") (name "Net-(D10-A)") (class "Default")
      (node (ref "C69") (pin "1") (pinfunction "1_1") (pintype "passive"))
      (node (ref "D10") (pin "2") (pinfunction "A_2") (pintype "passive"))
      (node (ref "L6") (pin "1") (pinfunction "1_1") (pintype "passive"))
      (node (ref "TP164") (pin "1") (pinfunction "1_1") (pintype "passive"))
      (node (ref "U21") (pin "2") (pinfunction "AC_2") (pintype "passive"))
    )
    (net (code "21") (name "Net-(D10-K)") (class "Default")
      (node (ref "C58") (pin "1") (pinfunction "1_1") (pintype "passive"))
      (node (ref "D10") (pin "1") (pinfunction "K_1") (pintype "passive"))
      (node (ref "D9") (pin "1") (pinfunction "K_1") (pintype "passive"))
      (node (ref "TP163") (pin "1") (pinfunction "1_1") (pintype "passive"))
      (node (ref "U20") (pin "3") (pinfunction "Vin_3") (pintype "passive"))
    )
    (net (code "22") (name "Net-(Q2-D)") (class "Default")
      (node (ref "Q2") (pin "3") (pinfunction "D_3") (pintype "passive"))
      (node (ref "R72") (pin "1") (pinfunction "1_1") (pintype "passive"))
      (node (ref "R75") (pin "1") (pinfunction "1_1") (pintype "passive"))
      (node (ref "TP151") (pin "1") (pinfunction "1_1") (pintype "passive"))
    )
    (net (code "23") (name "Net-(Q2-G)") (class "Default")
      (node (ref "Q2") (pin "1") (pinfunction "G_1") (pintype "passive"))
      (node (ref "R77") (pin "2") (pinfunction "2_2") (pintype "passive"))
      (node (ref "TP150") (pin "1") (pinfunction "1_1") (pintype "passive"))
      (node (ref "U25") (pin "8") (pinfunction "Y4_8") (pintype "output"))
    )
    (net (code "24") (name "Net-(Q3-B)") (class "Default")
      (node (ref "C54") (pin "2") (pinfunction "2_2") (pintype "passive"))
      (node (ref "Q3") (pin "1") (pinfunction "B_1") (pintype "passive"))
      (node (ref "R75") (pin "2") (pinfunction "2_2") (pintype "passive"))
      (node (ref "TP152") (pin "1") (pinfunction "1_1") (pintype "passive"))
    )
    (net (code "25") (name "Net-(Q3-E)") (class "Default")
      (node (ref "Q3") (pin "2") (pinfunction "E_2") (pintype "passive"))
      (node (ref "Q5") (pin "1") (pinfunction "B_1") (pintype "passive"))
      (node (ref "TP153") (pin "1") (pinfunction "1_1") (pintype "passive"))
    )
    (net (code "26") (name "Net-(Q4-C)") (class "Default")
      (node (ref "Q4") (pin "3") (pinfunction "C_3") (pintype "passive"))
      (node (ref "R69") (pin "2") (pinfunction "2_2") (pintype "passive"))
      (node (ref "TP148") (pin "1") (pinfunction "1_1") (pintype "passive"))
      (node (ref "U25") (pin "1") (pinfunction "A1_1") (pintype "input"))
    )
    (net (code "27") (name "Net-(Q5-E)") (class "Default")
      (node (ref "Q5") (pin "3") (pinfunction "E_3") (pintype "passive"))
      (node (ref "R76") (pin "1") (pinfunction "1_1") (pintype "passive"))
      (node (ref "TP187") (pin "1") (pinfunction "1_1") (pintype "passive"))
    )
    (net (code "28") (name "Net-(R65-Pad1)") (class "Default")
      (node (ref "R65") (pin "1") (pinfunction "1_1") (pintype "passive"))
      (node (ref "TP161") (pin "1") (pinfunction "1_1") (pintype "passive"))
      (node (ref "U19") (pin "1") (pinfunction "1_1") (pintype "passive"))
    )
    (net (code "29") (name "Net-(TVS1-A)") (class "Default")
      (node (ref "C68") (pin "1") (pinfunction "1_1") (pintype "passive"))
      (node (ref "CN7") (pin "3") (pinfunction "3_3") (pintype "passive"))
      (node (ref "TP177") (pin "1") (pinfunction "1_1") (pintype "passive"))
      (node (ref "TVS1") (pin "2") (pinfunction "A_2") (pintype "passive"))
      (node (ref "U28") (pin "3") (pinfunction "PSG_3") (pintype "passive"))
    )
    (net (code "30") (name "Net-(TVS1-K)") (class "Default")
      (node (ref "C68") (pin "2") (pinfunction "2_2") (pintype "passive"))
      (node (ref "CN7") (pin "4") (pinfunction "4_4") (pintype "passive"))
      (node (ref "TP175") (pin "1") (pinfunction "1_1") (pintype "passive"))
      (node (ref "TVS1") (pin "1") (pinfunction "K_1") (pintype "passive"))
      (node (ref "U28") (pin "1") (pinfunction "B_1") (pintype "passive"))
    )
    (net (code "31") (name "Net-(U17C-A3)") (class "Default")
      (node (ref "R50") (pin "2") (pinfunction "2_2") (pintype "passive"))
      (node (ref "TP144") (pin "1") (pinfunction "1_1") (pintype "passive"))
      (node (ref "U15") (pin "6") (pintype "passive"))
      (node (ref "U17") (pin "5") (pinfunction "A3_5") (pintype "input"))
    )
    (net (code "32") (name "Net-(U17D-A4)") (class "Default")
      (node (ref "TP141") (pin "1") (pinfunction "1_1") (pintype "passive"))
      (node (ref "U17") (pin "9") (pinfunction "A4_9") (pintype "input"))
      (node (ref "U23") (pin "4") (pinfunction "Y_4") (pintype "output"))
    )
    (net (code "33") (name "Net-(U20-ADJ)") (class "Default")
      (node (ref "R67") (pin "2") (pinfunction "2_2") (pintype "passive"))
      (node (ref "R68") (pin "1") (pinfunction "1_1") (pintype "passive"))
      (node (ref "TP162") (pin "1") (pinfunction "1_1") (pintype "passive"))
      (node (ref "U20") (pin "1") (pinfunction "ADJ_1") (pintype "passive"))
    )
    (net (code "34") (name "Net-(U21-+)") (class "Default")
      (node (ref "R72") (pin "2") (pinfunction "2_2") (pintype "passive"))
      (node (ref "R73") (pin "2") (pinfunction "2_2") (pintype "passive"))
      (node (ref "R74") (pin "2") (pinfunction "2_2") (pintype "passive"))
      (node (ref "R76") (pin "2") (pinfunction "2_2") (pintype "passive"))
      (node (ref "TP154") (pin "1") (pinfunction "1_1") (pintype "passive"))
      (node (ref "U21") (pin "1") (pinfunction "+_1") (pintype "passive"))
    )
    (net (code "35") (name "Net-(U22-AAM)") (class "Default")
      (node (ref "R96") (pin "2") (pinfunction "2_2") (pintype "passive"))
      (node (ref "TP185") (pin "1") (pinfunction "1_1") (pintype "passive"))
      (node (ref "U22") (pin "18") (pinfunction "AAM_18") (pintype "passive"))
    )
    (net (code "36") (name "Net-(U22-EN)") (class "Default")
      (node (ref "R48") (pin "2") (pinfunction "2_2") (pintype "passive"))
      (node (ref "TP184") (pin "1") (pinfunction "1_1") (pintype "passive"))
      (node (ref "U22") (pin "17") (pinfunction "EN_17") (pintype "passive"))
    )
    (net (code "37") (name "Net-(U22-FB)") (class "Default")
      (node (ref "R94") (pin "2") (pinfunction "2_2") (pintype "passive"))
      (node (ref "R95") (pin "1") (pinfunction "1_1") (pintype "passive"))
      (node (ref "TP186") (pin "1") (pinfunction "1_1") (pintype "passive"))
      (node (ref "U22") (pin "1") (pinfunction "FB_1") (pintype "passive"))
    )
    (net (code "38") (name "Net-(U25A-Y1)") (class "Default")
      (node (ref "TP147") (pin "1") (pinfunction "1_1") (pintype "passive"))
      (node (ref "U25") (pin "13") (pinfunction "A6_13") (pintype "input"))
      (node (ref "U25") (pin "2") (pinfunction "Y1_2") (pintype "output"))
    )
    (net (code "39") (name "Net-(U25D-A4)") (class "Default")
      (node (ref "R70") (pin "2") (pinfunction "2_2") (pintype "passive"))
      (node (ref "TP149") (pin "1") (pinfunction "1_1") (pintype "passive"))
      (node (ref "U16") (pin "6") (pintype "passive"))
      (node (ref "U25") (pin "9") (pinfunction "A4_9") (pintype "input"))
    )
    (net (code "40") (name "unconnected-(U17A-Y1-Pad2)") (class "Default")
      (node (ref "U17") (pin "2") (pinfunction "Y1_2") (pintype "output"))
    )
    (net (code "41") (name "unconnected-(U17B-Y2-Pad4)") (class "Default")
      (node (ref "U17") (pin "4") (pinfunction "Y2_4") (pintype "output"))
    )
    (net (code "42") (name "unconnected-(U17E-Y5-Pad10)") (class "Default")
      (node (ref "U17") (pin "10") (pinfunction "Y5_10") (pintype "output"))
    )
    (net (code "43") (name "unconnected-(U17F-Y6-Pad12)") (class "Default")
      (node (ref "U17") (pin "12") (pinfunction "Y6_12") (pintype "output"))
    )
    (net (code "44") (name "unconnected-(U22-BST-Pad11)") (class "Default")
      (node (ref "U22") (pin "11") (pinfunction "BST_11") (pintype "passive"))
    )
    (net (code "45") (name "unconnected-(U22-SW-Pad4)") (class "Default")
      (node (ref "U22") (pin "4") (pinfunction "SW_4") (pintype "passive"))
    )
    (net (code "46") (name "unconnected-(U22-SW-Pad5)") (class "Default")
      (node (ref "U22") (pin "5") (pinfunction "SW_5") (pintype "passive"))
    )
    (net (code "47") (name "unconnected-(U22-SW-Pad6)") (class "Default")
      (node (ref "U22") (pin "6") (pinfunction "SW_6") (pintype "passive"))
    )
    (net (code "48") (name "unconnected-(U22-Vcc-Pad2)") (class "Default")
      (node (ref "U22") (pin "2") (pinfunction "Vcc_2") (pintype "passive"))
    )
    (net (code "49") (name "unconnected-(U25B-Y2-Pad4)") (class "Default")
      (node (ref "U25") (pin "4") (pinfunction "Y2_4") (pintype "output"))
    )
    (net (code "50") (name "unconnected-(U25C-Y3-Pad6)") (class "Default")
      (node (ref "U25") (pin "6") (pinfunction "Y3_6") (pintype "output"))
    )
    (net (code "51") (name "unconnected-(U25E-Y5-Pad10)") (class "Default")
      (node (ref "U25") (pin "10") (pinfunction "Y5_10") (pintype "output"))
    )
  )
)
